# esp_ftdi_breakout.net
KiCad netlist of a schematic drawn in EAGLE
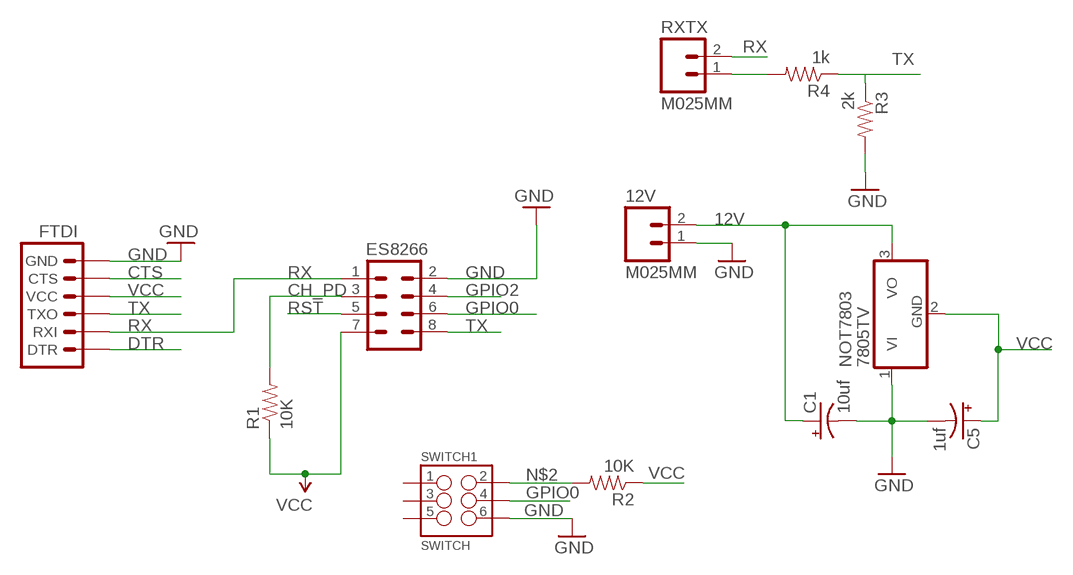
[diagram p0: schematic, sheet 1]

(export (version "E")
  (design (tool "Eeschema 10.0.6"))
  (components
    (comp (ref "12V")
      (value "M025MM")
      (footprint "eagle-import:SCREWTERMINAL-5MM-2")
      (libsource (lib "eagle-import") (part "M025MM"))
    )
    (comp (ref "C1")
      (value "10uf")
      (footprint "eagle-import:CPOL-RADIAL-10UF-25V")
      (libsource (lib "eagle-import") (part "CAP_POLPTH2"))
    )
    (comp (ref "C5")
      (value "1uf")
      (footprint "eagle-import:CPOL-RADIAL-10UF-25V")
      (libsource (lib "eagle-import") (part "CAP_POLPTH2"))
    )
    (comp (ref "ES8266")
      (value "M04X2")
      (footprint "eagle-import:2X4")
      (libsource (lib "eagle-import") (part "M04X2"))
    )
    (comp (ref "FTDI")
      (value "ARDUINO_SERIAL_PROGRAMPTH")
      (footprint "eagle-import:1X06")
      (libsource (lib "eagle-import") (part "ARDUINO_SERIAL_PROGRAMPTH"))
    )
    (comp (ref "NOT7803")
      (value "7805TV")
      (footprint "eagle-import:TO220V")
      (fields (field (name "SPICEPREFIX") "J"))
      (libsource (lib "eagle-import") (part "78TV05"))
    )
    (comp (ref "R1")
      (value "10K")
      (footprint "eagle-import:AXIAL-0.3")
      (libsource (lib "eagle-import") (part "1KOHM-1/4W-1%(PTH)"))
    )
    (comp (ref "R2")
      (value "10K")
      (footprint "eagle-import:AXIAL-0.3")
      (libsource (lib "eagle-import") (part "1KOHM-1/4W-1%(PTH)"))
    )
    (comp (ref "R3")
      (value "2k")
      (footprint "eagle-import:AXIAL-0.3")
      (libsource (lib "eagle-import") (part "1KOHM-1/4W-1%(PTH)"))
    )
    (comp (ref "R4")
      (value "1k")
      (footprint "eagle-import:AXIAL-0.3")
      (libsource (lib "eagle-import") (part "1KOHM-1/4W-1%(PTH)"))
    )
    (comp (ref "RXTX")
      (value "M025MM")
      (footprint "eagle-import:SCREWTERMINAL-5MM-2")
      (libsource (lib "eagle-import") (part "M025MM"))
    )
    (comp (ref "SWITCH1")
      (value "SWITCH")
      (footprint "eagle-import:2X3")
      (libsource (lib "eagle-import") (part "M03X2FEMALE"))
    )
  )
  (nets
    (net (code "1") (name "/12V") (class "Default")
      (node (ref "12V") (pin "2") (pinfunction "2_2") (pintype "passive"))
      (node (ref "C1") (pin "1") (pinfunction "+_1") (pintype "passive"))
      (node (ref "NOT7803") (pin "3") (pinfunction "VO_3") (pintype "passive"))
    )
    (net (code "2") (name "/CH_PD") (class "Default")
      (node (ref "ES8266") (pin "3") (pinfunction "3_3") (pintype "passive"))
      (node (ref "R1") (pin "P$2") (pinfunction "2_P$2") (pintype "passive"))
    )
    (net (code "3") (name "/CTS") (class "Default")
      (node (ref "FTDI") (pin "5") (pinfunction "CTS_5") (pintype "passive"))
    )
    (net (code "4") (name "/DTR") (class "Default")
      (node (ref "FTDI") (pin "1") (pinfunction "DTR_1") (pintype "passive"))
    )
    (net (code "5") (name "/GPIO0") (class "Default")
      (node (ref "ES8266") (pin "6") (pinfunction "6_6") (pintype "passive"))
      (node (ref "SWITCH1") (pin "4") (pinfunction "4_4") (pintype "bidirectional"))
    )
    (net (code "6") (name "/GPIO2") (class "Default")
      (node (ref "ES8266") (pin "4") (pinfunction "4_4") (pintype "passive"))
    )
    (net (code "7") (name "/N$2") (class "Default")
      (node (ref "R2") (pin "P$2") (pinfunction "2_P$2") (pintype "passive"))
      (node (ref "SWITCH1") (pin "2") (pinfunction "2_2") (pintype "bidirectional"))
    )
    (net (code "8") (name "/RST") (class "Default")
      (node (ref "ES8266") (pin "5") (pinfunction "5_5") (pintype "passive"))
    )
    (net (code "9") (name "/RX") (class "Default")
      (node (ref "ES8266") (pin "1") (pinfunction "1_1") (pintype "passive"))
      (node (ref "FTDI") (pin "2") (pinfunction "RXI_2") (pintype "passive"))
      (node (ref "RXTX") (pin "2") (pinfunction "2_2") (pintype "passive"))
    )
    (net (code "10") (name "/TX") (class "Default")
      (node (ref "ES8266") (pin "8") (pinfunction "8_8") (pintype "passive"))
      (node (ref "FTDI") (pin "3") (pinfunction "TXO_3") (pintype "passive"))
      (node (ref "R3") (pin "P$1") (pinfunction "1_P$1") (pintype "passive"))
      (node (ref "R4") (pin "P$1") (pinfunction "1_P$1") (pintype "passive"))
    )
    (net (code "11") (name "GND") (class "Default")
      (node (ref "12V") (pin "1") (pinfunction "1_1") (pintype "passive"))
      (node (ref "C1") (pin "2") (pinfunction "-_2") (pintype "passive"))
      (node (ref "C5") (pin "2") (pinfunction "-_2") (pintype "passive"))
      (node (ref "ES8266") (pin "2") (pinfunction "2_2") (pintype "passive"))
      (node (ref "FTDI") (pin "6") (pinfunction "GND_6") (pintype "passive"))
      (node (ref "NOT7803") (pin "1") (pinfunction "VI_1") (pintype "input"))
      (node (ref "R3") (pin "P$2") (pinfunction "2_P$2") (pintype "passive"))
      (node (ref "SWITCH1") (pin "6") (pinfunction "6_6") (pintype "bidirectional"))
    )
    (net (code "12") (name "Net-(R4-2)") (class "Default")
      (node (ref "R4") (pin "P$2") (pinfunction "2_P$2") (pintype "passive"))
      (node (ref "RXTX") (pin "1") (pinfunction "1_1") (pintype "passive"))
    )
    (net (code "13") (name "VCC") (class "Default")
      (node (ref "C5") (pin "1") (pinfunction "+_1") (pintype "passive"))
      (node (ref "ES8266") (pin "7") (pinfunction "7_7") (pintype "passive"))
      (node (ref "FTDI") (pin "4") (pinfunction "VCC_4") (pintype "passive"))
      (node (ref "NOT7803") (pin "2") (pinfunction "GND_2") (pintype "passive"))
      (node (ref "R1") (pin "P$1") (pinfunction "1_P$1") (pintype "passive"))
      (node (ref "R2") (pin "P$1") (pinfunction "1_P$1") (pintype "passive"))
    )
    (net (code "14") (name "unconnected-(SWITCH1-Pad1)") (class "Default")
      (node (ref "SWITCH1") (pin "1") (pinfunction "1_1") (pintype "bidirectional"))
    )
    (net (code "15") (name "unconnected-(SWITCH1-Pad3)") (class "Default")
      (node (ref "SWITCH1") (pin "3") (pinfunction "3_3") (pintype "bidirectional"))
    )
    (net (code "16") (name "unconnected-(SWITCH1-Pad5)") (class "Default")
      (node (ref "SWITCH1") (pin "5") (pinfunction "5_5") (pintype "bidirectional"))
    )
  )
)
